# Turn-On-Test.net
KiCad netlist of a schematic drawn in EAGLE
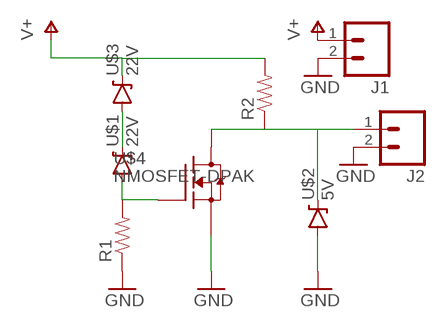
[diagram p0: schematic, sheet 1]

(export (version "E")
  (design (tool "Eeschema 10.0.6"))
  (components
    (comp (ref "J1")
      (value "M02PTH")
      (footprint "eagle-import:1X02")
      (libsource (lib "eagle-import") (part "M02PTH"))
    )
    (comp (ref "J2")
      (value "M02PTH")
      (footprint "eagle-import:1X02")
      (libsource (lib "eagle-import") (part "M02PTH"))
    )
    (comp (ref "R1")
      (value "RESISTOR0603-RES")
      (footprint "eagle-import:0603-RES")
      (libsource (lib "eagle-import") (part "RESISTOR0603-RES"))
    )
    (comp (ref "R2")
      (value "RESISTOR0603-RES")
      (footprint "eagle-import:0603-RES")
      (libsource (lib "eagle-import") (part "RESISTOR0603-RES"))
    )
    (comp (ref "U$1")
      (value "22V")
      (footprint "eagle-import:SOT23-3")
      (libsource (lib "eagle-import") (part "ZENER-SOT23"))
    )
    (comp (ref "U$2")
      (value "5V")
      (footprint "eagle-import:SOT23-3")
      (libsource (lib "eagle-import") (part "ZENER-SOT23"))
    )
    (comp (ref "U$3")
      (value "22V")
      (footprint "eagle-import:SOT23-3")
      (libsource (lib "eagle-import") (part "ZENER-SOT23"))
    )
    (comp (ref "U$4")
      (value "NMOSFET-DPAK")
      (footprint "eagle-import:DPAK")
      (libsource (lib "eagle-import") (part "NMOSFET-DPAK"))
    )
  )
  (nets
    (net (code "1") (name "GND") (class "Default")
      (node (ref "J1") (pin "2") (pinfunction "2_2") (pintype "passive"))
      (node (ref "J2") (pin "2") (pinfunction "2_2") (pintype "passive"))
      (node (ref "R1") (pin "1") (pinfunction "1_1") (pintype "passive"))
      (node (ref "U$2") (pin "1") (pinfunction "A_1") (pintype "passive"))
      (node (ref "U$4") (pin "3") (pinfunction "S_3") (pintype "passive"))
    )
    (net (code "2") (name "Net-(U$1-A)") (class "Default")
      (node (ref "R1") (pin "2") (pinfunction "2_2") (pintype "passive"))
      (node (ref "U$1") (pin "1") (pinfunction "A_1") (pintype "passive"))
      (node (ref "U$4") (pin "1") (pinfunction "G_1") (pintype "passive"))
    )
    (net (code "3") (name "Net-(U$1-C)") (class "Default")
      (node (ref "U$1") (pin "3") (pinfunction "C_3") (pintype "passive"))
      (node (ref "U$3") (pin "1") (pinfunction "A_1") (pintype "passive"))
    )
    (net (code "4") (name "Net-(U$2-C)") (class "Default")
      (node (ref "J2") (pin "1") (pinfunction "1_1") (pintype "passive"))
      (node (ref "R2") (pin "1") (pinfunction "1_1") (pintype "passive"))
      (node (ref "U$2") (pin "3") (pinfunction "C_3") (pintype "passive"))
      (node (ref "U$4") (pin "4") (pinfunction "D1_4") (pintype "passive"))
    )
    (net (code "5") (name "V+") (class "Default")
      (node (ref "J1") (pin "1") (pinfunction "1_1") (pintype "passive"))
      (node (ref "R2") (pin "2") (pinfunction "2_2") (pintype "passive"))
      (node (ref "U$3") (pin "3") (pinfunction "C_3") (pintype "passive"))
    )
  )
)
